# hackspace_con.net
KiCad netlist of a schematic drawn in EAGLE
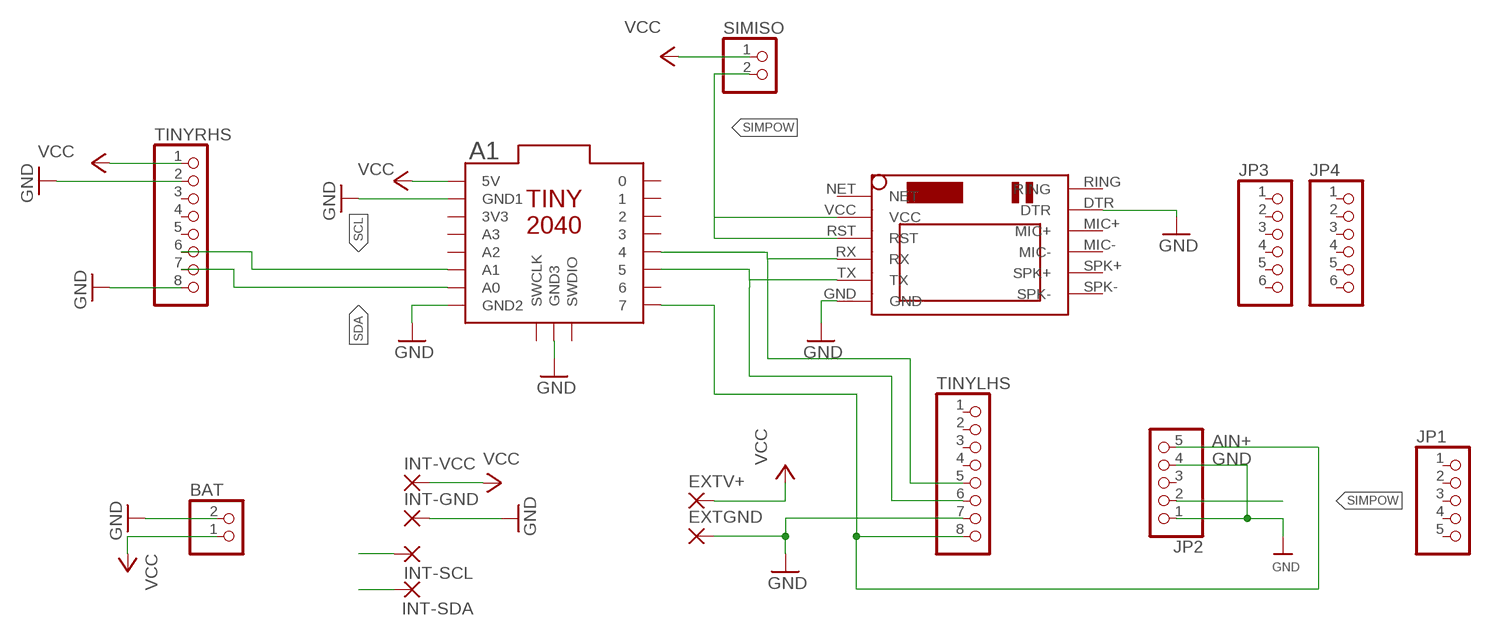
[diagram p0: schematic, sheet 1]

(export (version "E")
  (design (tool "Eeschema 10.0.6"))
  (components
    (comp (ref "A1")
      (value "TINY2040")
      (footprint "eagle-import:TINY2040")
      (libsource (lib "eagle-import") (part "TINY2040"))
    )
    (comp (ref "BAT")
      (value "JST_2PIN-THM-RA")
      (footprint "eagle-import:JST-PH-2-THM-RA")
      (libsource (lib "eagle-import") (part "JST_2PIN-THM-RA"))
    )
    (comp (ref "EXTGND")
      (value "SMD5")
      (footprint "eagle-import:SMD2,54-5,08")
      (libsource (lib "eagle-import") (part "SMD5"))
    )
    (comp (ref "EXTV+")
      (value "SMD5")
      (footprint "eagle-import:SMD2,54-5,08")
      (libsource (lib "eagle-import") (part "SMD5"))
    )
    (comp (ref "INT-GND")
      (value "3,17/1,1")
      (footprint "eagle-import:3,17_1,1")
      (libsource (lib "eagle-import") (part "3,17/1,1"))
    )
    (comp (ref "INT-SCL")
      (value "3,17/1,1")
      (footprint "eagle-import:3,17_1,1")
      (libsource (lib "eagle-import") (part "3,17/1,1"))
    )
    (comp (ref "INT-SDA")
      (value "3,17/1,1")
      (footprint "eagle-import:3,17_1,1")
      (libsource (lib "eagle-import") (part "3,17/1,1"))
    )
    (comp (ref "INT-VCC")
      (value "3,17/1,1")
      (footprint "eagle-import:3,17_1,1")
      (libsource (lib "eagle-import") (part "3,17/1,1"))
    )
    (comp (ref "JP1")
      (value "PINHD-1X5")
      (footprint "eagle-import:1X05")
      (libsource (lib "eagle-import") (part "PINHD-1X5"))
    )
    (comp (ref "JP2")
      (value "HEADER-1X570MIL")
      (footprint "eagle-import:1X05_ROUND_70")
      (libsource (lib "eagle-import") (part "HEADER-1X570MIL"))
    )
    (comp (ref "JP3")
      (value "PINHD-1X6")
      (footprint "eagle-import:1X06")
      (libsource (lib "eagle-import") (part "PINHD-1X6"))
    )
    (comp (ref "JP4")
      (value "PINHD-1X6")
      (footprint "eagle-import:1X06")
      (libsource (lib "eagle-import") (part "PINHD-1X6"))
    )
    (comp (ref "SIMISO")
      (value "PINHD-1X2")
      (footprint "eagle-import:1X02")
      (libsource (lib "eagle-import") (part "PINHD-1X2"))
    )
    (comp (ref "TINYLHS")
      (value "PINHD-1X8")
      (footprint "eagle-import:1X08")
      (libsource (lib "eagle-import") (part "PINHD-1X8"))
    )
    (comp (ref "TINYRHS")
      (value "PINHD-1X8")
      (footprint "eagle-import:1X08")
      (libsource (lib "eagle-import") (part "PINHD-1X8"))
    )
    (comp (ref "U$1")
      (value "SIM800LMODULE")
      (footprint "eagle-import:SIM800LMODULE")
      (libsource (lib "eagle-import") (part "SIM800LMODULE"))
    )
  )
  (nets
    (net (code "1") (name "/AIN+") (class "Default")
      (node (ref "A1") (pin "7") (pinfunction "7_7") (pintype "bidirectional"))
      (node (ref "JP2") (pin "5") (pinfunction "5_5") (pintype "passive"))
      (node (ref "TINYLHS") (pin "8") (pinfunction "8_8") (pintype "passive"))
    )
    (net (code "2") (name "GND") (class "Default")
      (node (ref "A1") (pin "GND1") (pinfunction "GND1_GND1") (pintype "bidirectional"))
      (node (ref "A1") (pin "GND2") (pinfunction "GND2_GND2") (pintype "bidirectional"))
      (node (ref "A1") (pin "GND3") (pinfunction "GND3_GND3") (pintype "bidirectional"))
      (node (ref "BAT") (pin "2") (pinfunction "1_2") (pintype "passive"))
      (node (ref "EXTGND") (pin "1") (pinfunction "P_1") (pintype "passive"))
      (node (ref "INT-GND") (pin "1") (pinfunction "P_1") (pintype "passive"))
      (node (ref "JP2") (pin "1") (pinfunction "1_1") (pintype "passive"))
      (node (ref "JP2") (pin "4") (pinfunction "4_4") (pintype "passive"))
      (node (ref "TINYLHS") (pin "7") (pinfunction "7_7") (pintype "passive"))
      (node (ref "TINYRHS") (pin "2") (pinfunction "2_2") (pintype "passive"))
      (node (ref "TINYRHS") (pin "8") (pinfunction "8_8") (pintype "passive"))
      (node (ref "U$1") (pin "DTR") (pinfunction "DTR_DTR") (pintype "bidirectional"))
      (node (ref "U$1") (pin "GND") (pinfunction "GND_GND") (pintype "bidirectional"))
    )
    (net (code "3") (name "Net-(A1-Pad4)") (class "Default")
      (node (ref "A1") (pin "4") (pinfunction "4_4") (pintype "bidirectional"))
      (node (ref "TINYLHS") (pin "5") (pinfunction "5_5") (pintype "passive"))
      (node (ref "U$1") (pin "RX") (pinfunction "RX_RX") (pintype "bidirectional"))
    )
    (net (code "4") (name "Net-(A1-Pad5)") (class "Default")
      (node (ref "A1") (pin "5") (pinfunction "5_5") (pintype "bidirectional"))
      (node (ref "TINYLHS") (pin "6") (pinfunction "6_6") (pintype "passive"))
      (node (ref "U$1") (pin "TX") (pinfunction "TX_TX") (pintype "bidirectional"))
    )
    (net (code "5") (name "SCL") (class "Default")
      (node (ref "A1") (pin "A1") (pinfunction "A1_A1") (pintype "bidirectional"))
      (node (ref "INT-SCL") (pin "1") (pinfunction "P_1") (pintype "passive"))
      (node (ref "TINYRHS") (pin "6") (pinfunction "6_6") (pintype "passive"))
    )
    (net (code "6") (name "SDA") (class "Default")
      (node (ref "A1") (pin "A0") (pinfunction "A0_A0") (pintype "bidirectional"))
      (node (ref "INT-SDA") (pin "1") (pinfunction "P_1") (pintype "passive"))
      (node (ref "TINYRHS") (pin "7") (pinfunction "7_7") (pintype "passive"))
    )
    (net (code "7") (name "SIMPOW") (class "Default")
      (node (ref "JP2") (pin "2") (pinfunction "2_2") (pintype "passive"))
      (node (ref "SIMISO") (pin "2") (pinfunction "2_2") (pintype "passive"))
      (node (ref "U$1") (pin "RST") (pinfunction "RST_RST") (pintype "bidirectional"))
      (node (ref "U$1") (pin "VCC") (pinfunction "VCC_VCC") (pintype "bidirectional"))
    )
    (net (code "8") (name "VCC") (class "Default")
      (node (ref "A1") (pin "5V") (pinfunction "5V_5V") (pintype "bidirectional"))
      (node (ref "BAT") (pin "1") (pinfunction "2_1") (pintype "passive"))
      (node (ref "EXTV+") (pin "1") (pinfunction "P_1") (pintype "passive"))
      (node (ref "INT-VCC") (pin "1") (pinfunction "P_1") (pintype "passive"))
      (node (ref "SIMISO") (pin "1") (pinfunction "1_1") (pintype "passive"))
      (node (ref "TINYRHS") (pin "1") (pinfunction "1_1") (pintype "passive"))
    )
    (net (code "9") (name "unconnected-(A1-Pad0)") (class "Default")
      (node (ref "A1") (pin "0") (pinfunction "0_0") (pintype "bidirectional"))
    )
    (net (code "10") (name "unconnected-(A1-Pad1)") (class "Default")
      (node (ref "A1") (pin "1") (pinfunction "1_1") (pintype "bidirectional"))
    )
    (net (code "11") (name "unconnected-(A1-Pad2)") (class "Default")
      (node (ref "A1") (pin "2") (pinfunction "2_2") (pintype "bidirectional"))
    )
    (net (code "12") (name "unconnected-(A1-Pad3)") (class "Default")
      (node (ref "A1") (pin "3") (pinfunction "3_3") (pintype "bidirectional"))
    )
    (net (code "13") (name "unconnected-(A1-Pad3V3)") (class "Default")
      (node (ref "A1") (pin "3V3") (pinfunction "3V3_3V3") (pintype "bidirectional"))
    )
    (net (code "14") (name "unconnected-(A1-Pad6)") (class "Default")
      (node (ref "A1") (pin "6") (pinfunction "6_6") (pintype "bidirectional"))
    )
    (net (code "15") (name "unconnected-(A1-PadA2)") (class "Default")
      (node (ref "A1") (pin "A2") (pinfunction "A2_A2") (pintype "bidirectional"))
    )
    (net (code "16") (name "unconnected-(A1-PadA3)") (class "Default")
      (node (ref "A1") (pin "A3") (pinfunction "A3_A3") (pintype "bidirectional"))
    )
    (net (code "17") (name "unconnected-(A1-PadSWCLK)") (class "Default")
      (node (ref "A1") (pin "SWCLK") (pinfunction "SWCLK_SWCLK") (pintype "bidirectional"))
    )
    (net (code "18") (name "unconnected-(A1-PadSWDIO)") (class "Default")
      (node (ref "A1") (pin "SWDIO") (pinfunction "SWDIO_SWDIO") (pintype "bidirectional"))
    )
    (net (code "19") (name "unconnected-(JP1-Pad1)") (class "Default")
      (node (ref "JP1") (pin "1") (pinfunction "1_1") (pintype "passive"))
    )
    (net (code "20") (name "unconnected-(JP1-Pad2)") (class "Default")
      (node (ref "JP1") (pin "2") (pinfunction "2_2") (pintype "passive"))
    )
    (net (code "21") (name "unconnected-(JP1-Pad3)") (class "Default")
      (node (ref "JP1") (pin "3") (pinfunction "3_3") (pintype "passive"))
    )
    (net (code "22") (name "unconnected-(JP1-Pad4)") (class "Default")
      (node (ref "JP1") (pin "4") (pinfunction "4_4") (pintype "passive"))
    )
    (net (code "23") (name "unconnected-(JP1-Pad5)") (class "Default")
      (node (ref "JP1") (pin "5") (pinfunction "5_5") (pintype "passive"))
    )
    (net (code "24") (name "unconnected-(JP2-Pad3)") (class "Default")
      (node (ref "JP2") (pin "3") (pinfunction "3_3") (pintype "passive"))
    )
    (net (code "25") (name "unconnected-(JP3-Pad1)") (class "Default")
      (node (ref "JP3") (pin "1") (pinfunction "1_1") (pintype "passive"))
    )
    (net (code "26") (name "unconnected-(JP3-Pad2)") (class "Default")
      (node (ref "JP3") (pin "2") (pinfunction "2_2") (pintype "passive"))
    )
    (net (code "27") (name "unconnected-(JP3-Pad3)") (class "Default")
      (node (ref "JP3") (pin "3") (pinfunction "3_3") (pintype "passive"))
    )
    (net (code "28") (name "unconnected-(JP3-Pad4)") (class "Default")
      (node (ref "JP3") (pin "4") (pinfunction "4_4") (pintype "passive"))
    )
    (net (code "29") (name "unconnected-(JP3-Pad5)") (class "Default")
      (node (ref "JP3") (pin "5") (pinfunction "5_5") (pintype "passive"))
    )
    (net (code "30") (name "unconnected-(JP3-Pad6)") (class "Default")
      (node (ref "JP3") (pin "6") (pinfunction "6_6") (pintype "passive"))
    )
    (net (code "31") (name "unconnected-(JP4-Pad1)") (class "Default")
      (node (ref "JP4") (pin "1") (pinfunction "1_1") (pintype "passive"))
    )
    (net (code "32") (name "unconnected-(JP4-Pad2)") (class "Default")
      (node (ref "JP4") (pin "2") (pinfunction "2_2") (pintype "passive"))
    )
    (net (code "33") (name "unconnected-(JP4-Pad3)") (class "Default")
      (node (ref "JP4") (pin "3") (pinfunction "3_3") (pintype "passive"))
    )
    (net (code "34") (name "unconnected-(JP4-Pad4)") (class "Default")
      (node (ref "JP4") (pin "4") (pinfunction "4_4") (pintype "passive"))
    )
    (net (code "35") (name "unconnected-(JP4-Pad5)") (class "Default")
      (node (ref "JP4") (pin "5") (pinfunction "5_5") (pintype "passive"))
    )
    (net (code "36") (name "unconnected-(JP4-Pad6)") (class "Default")
      (node (ref "JP4") (pin "6") (pinfunction "6_6") (pintype "passive"))
    )
    (net (code "37") (name "unconnected-(TINYLHS-Pad1)") (class "Default")
      (node (ref "TINYLHS") (pin "1") (pinfunction "1_1") (pintype "passive"))
    )
    (net (code "38") (name "unconnected-(TINYLHS-Pad2)") (class "Default")
      (node (ref "TINYLHS") (pin "2") (pinfunction "2_2") (pintype "passive"))
    )
    (net (code "39") (name "unconnected-(TINYLHS-Pad3)") (class "Default")
      (node (ref "TINYLHS") (pin "3") (pinfunction "3_3") (pintype "passive"))
    )
    (net (code "40") (name "unconnected-(TINYLHS-Pad4)") (class "Default")
      (node (ref "TINYLHS") (pin "4") (pinfunction "4_4") (pintype "passive"))
    )
    (net (code "41") (name "unconnected-(TINYRHS-Pad3)") (class "Default")
      (node (ref "TINYRHS") (pin "3") (pinfunction "3_3") (pintype "passive"))
    )
    (net (code "42") (name "unconnected-(TINYRHS-Pad4)") (class "Default")
      (node (ref "TINYRHS") (pin "4") (pinfunction "4_4") (pintype "passive"))
    )
    (net (code "43") (name "unconnected-(TINYRHS-Pad5)") (class "Default")
      (node (ref "TINYRHS") (pin "5") (pinfunction "5_5") (pintype "passive"))
    )
    (net (code "44") (name "unconnected-(U$1-PadMIC+)") (class "Default")
      (node (ref "U$1") (pin "MIC+") (pinfunction "MIC+_MIC+") (pintype "bidirectional"))
    )
    (net (code "45") (name "unconnected-(U$1-PadMIC-)") (class "Default")
      (node (ref "U$1") (pin "MIC-") (pinfunction "MIC-_MIC-") (pintype "bidirectional"))
    )
    (net (code "46") (name "unconnected-(U$1-PadNET)") (class "Default")
      (node (ref "U$1") (pin "NET") (pinfunction "NET_NET") (pintype "bidirectional"))
    )
    (net (code "47") (name "unconnected-(U$1-PadRING)") (class "Default")
      (node (ref "U$1") (pin "RING") (pinfunction "RING_RING") (pintype "bidirectional"))
    )
    (net (code "48") (name "unconnected-(U$1-PadSPK+)") (class "Default")
      (node (ref "U$1") (pin "SPK+") (pinfunction "SPK+_SPK+") (pintype "bidirectional"))
    )
    (net (code "49") (name "unconnected-(U$1-PadSPK-)") (class "Default")
      (node (ref "U$1") (pin "SPK-") (pinfunction "SPK-_SPK-") (pintype "bidirectional"))
    )
  )
)
